# 08_MSM8916_RF.net
KiCad netlist of a schematic drawn in Altium Designer
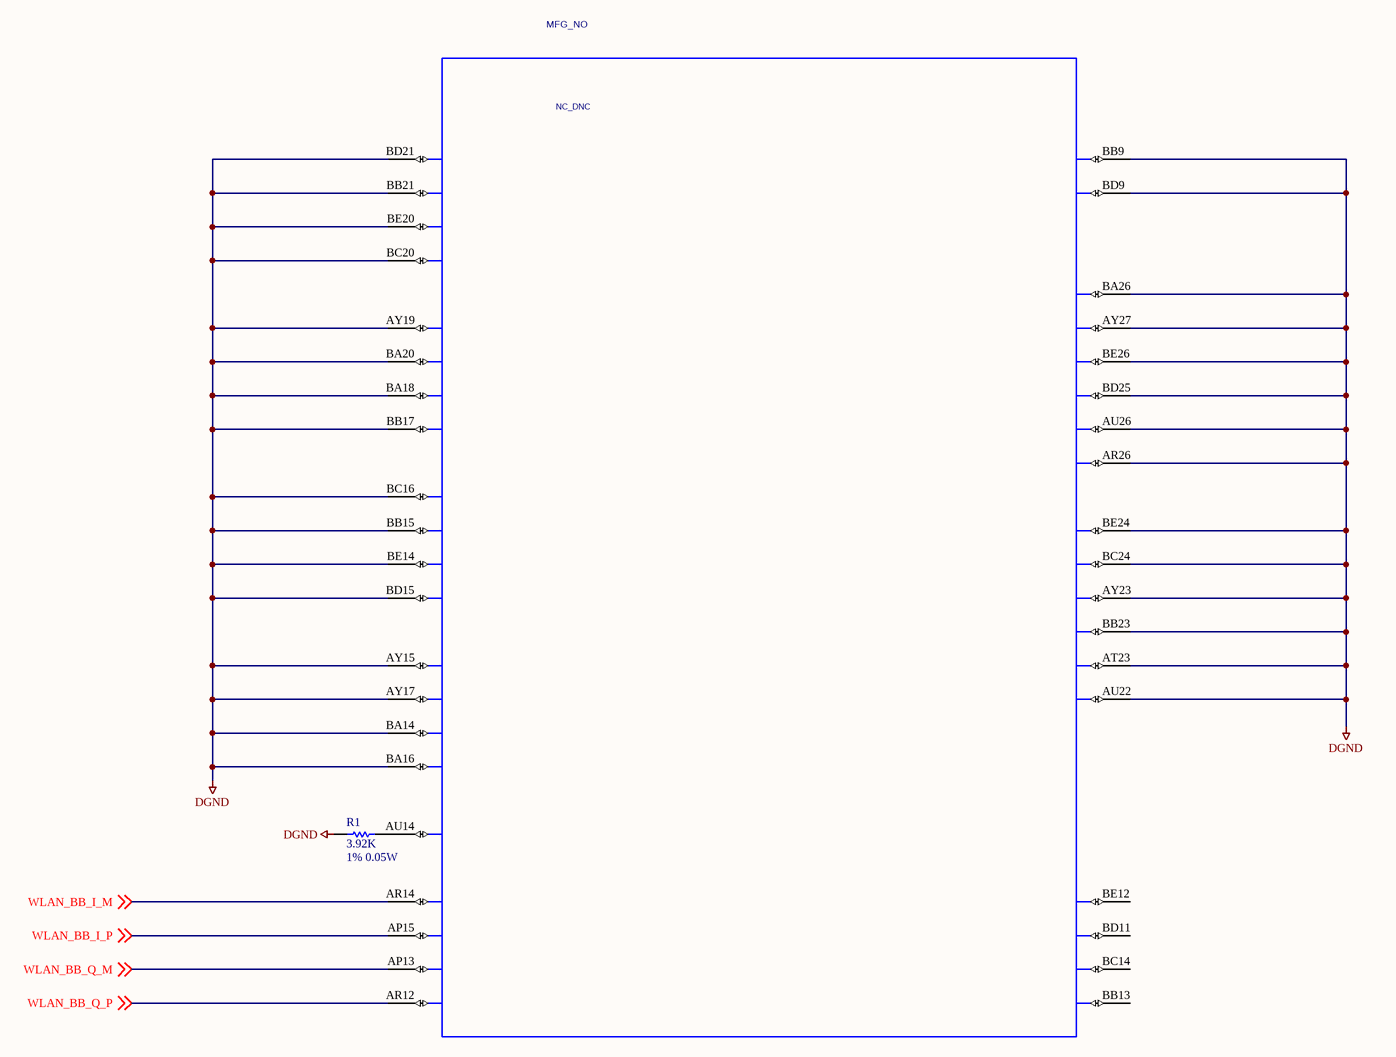
[diagram p0: 08_MSM8916_RF.SchDoc]

(export (version "E")
  (design (tool "Eeschema 10.0.6"))
  (components
    (comp (ref "R1")
      (value "3.92K")
      (footprint "r0402")
      (description "Resistor")
      (fields (field (name "ALTIUM_VALUE") "1% 0.05W") (field (name "PUBLISHER") "Altium Limited"))
      (libsource (lib "Miscellaneous Devices") (part "Res1"))
    )
    (comp (ref "U1")
      (value "ASIC_MSM8936_760PIN")
      (footprint "MSM-8916-0-760NSP-TR-00-0")
      (fields
        (field (name "PART_NUMBER") "MCN_NO")
        (field (name "SYMNAME") "NC_DNC")
        (field (name "PART_ID") "MFG_NO")
      )
      (libsource (lib "MSM8916_DRAM_PMIC_REF_Library") (part "ASIC_MSM8936_760PIN"))
    )
  )
  (nets
    (net (code "1") (name "DGND") (class "Default")
      (node (ref "R1") (pin "1") (pinfunction "1_1") (pintype "passive"))
      (node (ref "U1") (pin "AR26") (pinfunction "TXDAC0_VREF_AR26") (pintype "bidirectional"))
      (node (ref "U1") (pin "AT23") (pinfunction "TXDAC1_IREF_AT23") (pintype "bidirectional"))
      (node (ref "U1") (pin "AU22") (pinfunction "TXDAC1_VREF_AU22") (pintype "bidirectional"))
      (node (ref "U1") (pin "AU26") (pinfunction "TXDAC0_IREF_AU26") (pintype "bidirectional"))
      (node (ref "U1") (pin "AY15") (pinfunction "BBRX1_AY15") (pintype "bidirectional"))
      (node (ref "U1") (pin "AY17") (pinfunction "BBRX2_AY17") (pintype "bidirectional"))
      (node (ref "U1") (pin "AY19") (pinfunction "BBRX_I_IN_CH1_AY19") (pintype "bidirectional"))
      (node (ref "U1") (pin "AY23") (pinfunction "TXDAC1_QM_AY23") (pintype "bidirectional"))
      (node (ref "U1") (pin "AY27") (pinfunction "TXDAC0_IP_AY27") (pintype "bidirectional"))
      (node (ref "U1") (pin "BA14") (pinfunction "BBRX3_BA14") (pintype "bidirectional"))
      (node (ref "U1") (pin "BA16") (pinfunction "BBRX4_BA16") (pintype "bidirectional"))
      (node (ref "U1") (pin "BA18") (pinfunction "BBRX_I_QN_CH1_BA18") (pintype "bidirectional"))
      (node (ref "U1") (pin "BA20") (pinfunction "BBRX_I_IP_CH1_BA20") (pintype "bidirectional"))
      (node (ref "U1") (pin "BA26") (pinfunction "TXDAC0_IM_BA26") (pintype "bidirectional"))
      (node (ref "U1") (pin "BB15") (pinfunction "BBRX_I_IP_CH2_BB15") (pintype "bidirectional"))
      (node (ref "U1") (pin "BB17") (pinfunction "BBRX_I_QP_CH1_BB17") (pintype "bidirectional"))
      (node (ref "U1") (pin "BB21") (pinfunction "BBRX_I_IP_CH0_BB21") (pintype "bidirectional"))
      (node (ref "U1") (pin "BB23") (pinfunction "TXDAC1_QP_BB23") (pintype "bidirectional"))
      (node (ref "U1") (pin "BB9") (pinfunction "GRFC1_BB9") (pintype "bidirectional"))
      (node (ref "U1") (pin "BC16") (pinfunction "BBRX_I_IN_CH2_BC16") (pintype "bidirectional"))
      (node (ref "U1") (pin "BC20") (pinfunction "BBRX_I_QP_CH0_BC20") (pintype "bidirectional"))
      (node (ref "U1") (pin "BC24") (pinfunction "TXDAC1_IP_BC24") (pintype "bidirectional"))
      (node (ref "U1") (pin "BD15") (pinfunction "BBRX_I_QP_CH2_BD15") (pintype "bidirectional"))
      (node (ref "U1") (pin "BD21") (pinfunction "BBRX_I_IN_CH0_BD21") (pintype "bidirectional"))
      (node (ref "U1") (pin "BD25") (pinfunction "TXDAC0_QP_BD25") (pintype "bidirectional"))
      (node (ref "U1") (pin "BD9") (pinfunction "GRFC2_BD9") (pintype "bidirectional"))
      (node (ref "U1") (pin "BE14") (pinfunction "BBRX_I_QN_CH2_BE14") (pintype "bidirectional"))
      (node (ref "U1") (pin "BE20") (pinfunction "BBRX_I_QN_CH0_BE20") (pintype "bidirectional"))
      (node (ref "U1") (pin "BE24") (pinfunction "TXDAC1_IM_BE24") (pintype "bidirectional"))
      (node (ref "U1") (pin "BE26") (pinfunction "TXDAC0_QM_BE26") (pintype "bidirectional"))
    )
    (net (code "2") (name "Net-(U1F-WLAN_RSET)") (class "Default")
      (node (ref "R1") (pin "2") (pinfunction "2_2") (pintype "passive"))
      (node (ref "U1") (pin "AU14") (pinfunction "WLAN_RSET_AU14") (pintype "bidirectional"))
    )
    (net (code "3") (name "WLAN_BB_I_M") (class "Default")
      (node (ref "U1") (pin "AR14") (pinfunction "WLAN_IN_AR14") (pintype "bidirectional"))
    )
    (net (code "4") (name "WLAN_BB_I_P") (class "Default")
      (node (ref "U1") (pin "AP15") (pinfunction "WLAN_IP_AP15") (pintype "bidirectional"))
    )
    (net (code "5") (name "WLAN_BB_Q_M") (class "Default")
      (node (ref "U1") (pin "AP13") (pinfunction "WLAN_QN_AP13") (pintype "bidirectional"))
    )
    (net (code "6") (name "WLAN_BB_Q_P") (class "Default")
      (node (ref "U1") (pin "AR12") (pinfunction "WLAN_QP_AR12") (pintype "bidirectional"))
    )
    (net (code "7") (name "unconnected-(U1F-GPS_BBI-PadBE12)") (class "Default")
      (node (ref "U1") (pin "BE12") (pinfunction "GPS_BBI_BE12") (pintype "bidirectional"))
    )
    (net (code "8") (name "unconnected-(U1F-GPS_BBI2-PadBD11)") (class "Default")
      (node (ref "U1") (pin "BD11") (pinfunction "GPS_BBI2_BD11") (pintype "bidirectional"))
    )
    (net (code "9") (name "unconnected-(U1F-GPS_BBQ-PadBC14)") (class "Default")
      (node (ref "U1") (pin "BC14") (pinfunction "GPS_BBQ_BC14") (pintype "bidirectional"))
    )
    (net (code "10") (name "unconnected-(U1F-GPS_BBQ2-PadBB13)") (class "Default")
      (node (ref "U1") (pin "BB13") (pinfunction "GPS_BBQ2_BB13") (pintype "bidirectional"))
    )
  )
)
